# VGA_Connector.net
KiCad netlist of a schematic drawn in EAGLE
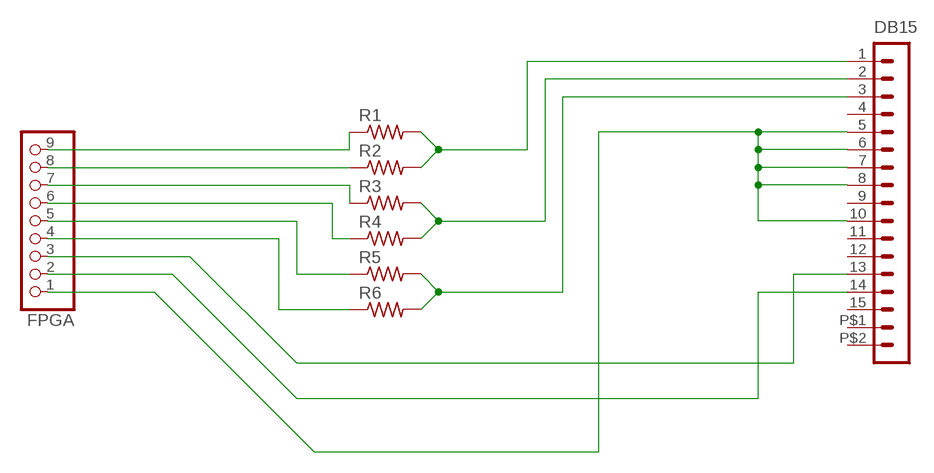
[diagram p0: schematic, sheet 1]

(export (version "E")
  (design (tool "Eeschema 10.0.6"))
  (components
    (comp (ref "DB15")
      (value "CON-DSUB-15-VGA")
      (footprint "eagle-import:181-015-212-171")
      (libsource (lib "eagle-import") (part "CON-DSUB-15-VGA"))
    )
    (comp (ref "FPGA")
      (value "PINHD-1X9/90")
      (footprint "eagle-import:1X09_90")
      (libsource (lib "eagle-import") (part "PINHD-1X9/90"))
    )
    (comp (ref "R1")
      (value "R-US_0207/10")
      (footprint "eagle-import:0207_10")
      (libsource (lib "eagle-import") (part "R-US_0207/10"))
    )
    (comp (ref "R2")
      (value "R-US_0207/10")
      (footprint "eagle-import:0207_10")
      (libsource (lib "eagle-import") (part "R-US_0207/10"))
    )
    (comp (ref "R3")
      (value "R-US_0207/10")
      (footprint "eagle-import:0207_10")
      (libsource (lib "eagle-import") (part "R-US_0207/10"))
    )
    (comp (ref "R4")
      (value "R-US_0207/10")
      (footprint "eagle-import:0207_10")
      (libsource (lib "eagle-import") (part "R-US_0207/10"))
    )
    (comp (ref "R5")
      (value "R-US_0207/10")
      (footprint "eagle-import:0207_10")
      (libsource (lib "eagle-import") (part "R-US_0207/10"))
    )
    (comp (ref "R6")
      (value "R-US_0207/10")
      (footprint "eagle-import:0207_10")
      (libsource (lib "eagle-import") (part "R-US_0207/10"))
    )
  )
  (nets
    (net (code "1") (name "Net-(DB15-Pad1)") (class "Default")
      (node (ref "DB15") (pin "1") (pinfunction "1_1") (pintype "passive"))
      (node (ref "R1") (pin "2") (pinfunction "2_2") (pintype "passive"))
      (node (ref "R2") (pin "2") (pinfunction "2_2") (pintype "passive"))
    )
    (net (code "2") (name "Net-(DB15-Pad2)") (class "Default")
      (node (ref "DB15") (pin "2") (pinfunction "2_2") (pintype "passive"))
      (node (ref "R3") (pin "2") (pinfunction "2_2") (pintype "passive"))
      (node (ref "R4") (pin "2") (pinfunction "2_2") (pintype "passive"))
    )
    (net (code "3") (name "Net-(DB15-Pad3)") (class "Default")
      (node (ref "DB15") (pin "3") (pinfunction "3_3") (pintype "passive"))
      (node (ref "R5") (pin "2") (pinfunction "2_2") (pintype "passive"))
      (node (ref "R6") (pin "2") (pinfunction "2_2") (pintype "passive"))
    )
    (net (code "4") (name "Net-(DB15-Pad10)") (class "Default")
      (node (ref "DB15") (pin "10") (pinfunction "10_10") (pintype "passive"))
      (node (ref "DB15") (pin "5") (pinfunction "5_5") (pintype "passive"))
      (node (ref "DB15") (pin "6") (pinfunction "6_6") (pintype "passive"))
      (node (ref "DB15") (pin "7") (pinfunction "7_7") (pintype "passive"))
      (node (ref "DB15") (pin "8") (pinfunction "8_8") (pintype "passive"))
      (node (ref "FPGA") (pin "1") (pinfunction "1_1") (pintype "passive"))
    )
    (net (code "5") (name "Net-(DB15-Pad13)") (class "Default")
      (node (ref "DB15") (pin "13") (pinfunction "13_13") (pintype "passive"))
      (node (ref "FPGA") (pin "3") (pinfunction "3_3") (pintype "passive"))
    )
    (net (code "6") (name "Net-(DB15-Pad14)") (class "Default")
      (node (ref "DB15") (pin "14") (pinfunction "14_14") (pintype "passive"))
      (node (ref "FPGA") (pin "2") (pinfunction "2_2") (pintype "passive"))
    )
    (net (code "7") (name "Net-(FPGA-Pad4)") (class "Default")
      (node (ref "FPGA") (pin "4") (pinfunction "4_4") (pintype "passive"))
      (node (ref "R6") (pin "1") (pinfunction "1_1") (pintype "passive"))
    )
    (net (code "8") (name "Net-(FPGA-Pad5)") (class "Default")
      (node (ref "FPGA") (pin "5") (pinfunction "5_5") (pintype "passive"))
      (node (ref "R5") (pin "1") (pinfunction "1_1") (pintype "passive"))
    )
    (net (code "9") (name "Net-(FPGA-Pad6)") (class "Default")
      (node (ref "FPGA") (pin "6") (pinfunction "6_6") (pintype "passive"))
      (node (ref "R4") (pin "1") (pinfunction "1_1") (pintype "passive"))
    )
    (net (code "10") (name "Net-(FPGA-Pad7)") (class "Default")
      (node (ref "FPGA") (pin "7") (pinfunction "7_7") (pintype "passive"))
      (node (ref "R3") (pin "1") (pinfunction "1_1") (pintype "passive"))
    )
    (net (code "11") (name "Net-(FPGA-Pad8)") (class "Default")
      (node (ref "FPGA") (pin "8") (pinfunction "8_8") (pintype "passive"))
      (node (ref "R2") (pin "1") (pinfunction "1_1") (pintype "passive"))
    )
    (net (code "12") (name "Net-(FPGA-Pad9)") (class "Default")
      (node (ref "FPGA") (pin "9") (pinfunction "9_9") (pintype "passive"))
      (node (ref "R1") (pin "1") (pinfunction "1_1") (pintype "passive"))
    )
    (net (code "13") (name "unconnected-(DB15-16-PadP$1)") (class "Default")
      (node (ref "DB15") (pin "P$1") (pinfunction "16_P$1") (pintype "passive"))
    )
    (net (code "14") (name "unconnected-(DB15-17-PadP$2)") (class "Default")
      (node (ref "DB15") (pin "P$2") (pinfunction "17_P$2") (pintype "passive"))
    )
    (net (code "15") (name "unconnected-(DB15-Pad4)") (class "Default")
      (node (ref "DB15") (pin "4") (pinfunction "4_4") (pintype "passive"))
    )
    (net (code "16") (name "unconnected-(DB15-Pad9)") (class "Default")
      (node (ref "DB15") (pin "9") (pinfunction "9_9") (pintype "passive"))
    )
    (net (code "17") (name "unconnected-(DB15-Pad11)") (class "Default")
      (node (ref "DB15") (pin "11") (pinfunction "11_11") (pintype "passive"))
    )
    (net (code "18") (name "unconnected-(DB15-Pad12)") (class "Default")
      (node (ref "DB15") (pin "12") (pinfunction "12_12") (pintype "passive"))
    )
    (net (code "19") (name "unconnected-(DB15-Pad15)") (class "Default")
      (node (ref "DB15") (pin "15") (pinfunction "15_15") (pintype "passive"))
    )
  )
)
